# MainBoard_Sheet1.net
KiCad netlist of a schematic drawn in Altium Designer
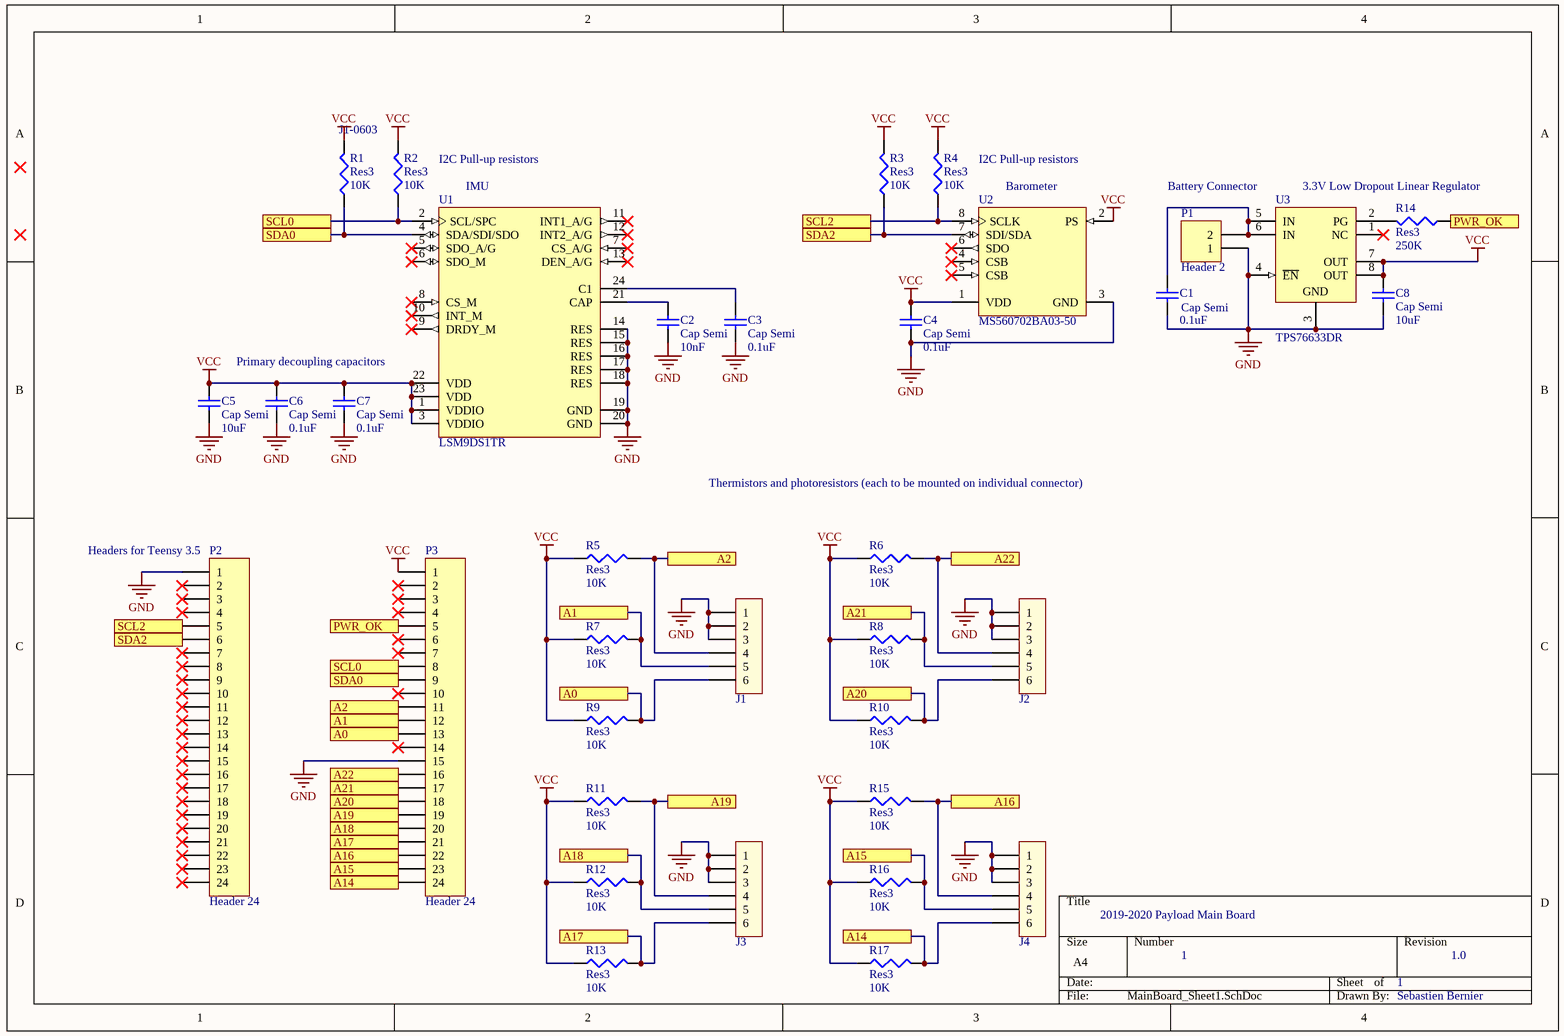
[diagram p0: MainBoard_Sheet1.SchDoc]

(export (version "E")
  (design (tool "Eeschema 10.0.6"))
  (components
    (comp (ref "C1")
      (value "Cap Semi")
      (footprint "C1206")
      (description "Capacitor (Semiconductor SIM Model)")
      (fields (field (name "ALTIUM_VALUE") "0.1uF") (field (name "PUBLISHER") "Altium Limited"))
      (libsource (lib "Miscellaneous Devices") (part "Cap Semi"))
    )
    (comp (ref "C2")
      (value "Cap Semi")
      (footprint "C1206")
      (description "Capacitor (Semiconductor SIM Model)")
      (fields (field (name "ALTIUM_VALUE") "10nF") (field (name "PUBLISHER") "Altium Limited"))
      (libsource (lib "Miscellaneous Devices") (part "Cap Semi"))
    )
    (comp (ref "C3")
      (value "Cap Semi")
      (footprint "C1206")
      (description "Capacitor (Semiconductor SIM Model)")
      (fields (field (name "ALTIUM_VALUE") "0.1uF") (field (name "PUBLISHER") "Altium Limited"))
      (libsource (lib "Miscellaneous Devices") (part "Cap Semi"))
    )
    (comp (ref "C4")
      (value "Cap Semi")
      (footprint "C1206")
      (description "Capacitor (Semiconductor SIM Model)")
      (fields (field (name "ALTIUM_VALUE") "0.1uF") (field (name "PUBLISHER") "Altium Limited"))
      (libsource (lib "Miscellaneous Devices") (part "Cap Semi"))
    )
    (comp (ref "C5")
      (value "Cap Semi")
      (footprint "C1206")
      (description "Capacitor (Semiconductor SIM Model)")
      (fields (field (name "ALTIUM_VALUE") "10uF") (field (name "PUBLISHER") "Altium Limited"))
      (libsource (lib "Miscellaneous Devices") (part "Cap Semi"))
    )
    (comp (ref "C6")
      (value "Cap Semi")
      (footprint "C1206")
      (description "Capacitor (Semiconductor SIM Model)")
      (fields (field (name "ALTIUM_VALUE") "0.1uF") (field (name "PUBLISHER") "Altium Limited"))
      (libsource (lib "Miscellaneous Devices") (part "Cap Semi"))
    )
    (comp (ref "C7")
      (value "Cap Semi")
      (footprint "C1206")
      (description "Capacitor (Semiconductor SIM Model)")
      (fields (field (name "ALTIUM_VALUE") "0.1uF") (field (name "PUBLISHER") "Altium Limited"))
      (libsource (lib "Miscellaneous Devices") (part "Cap Semi"))
    )
    (comp (ref "C8")
      (value "Cap Semi")
      (footprint "C1206")
      (description "Capacitor (Semiconductor SIM Model)")
      (fields (field (name "ALTIUM_VALUE") "10uF") (field (name "PUBLISHER") "Altium Limited"))
      (libsource (lib "Miscellaneous Devices") (part "Cap Semi"))
    )
    (comp (ref "J1")
      (value "0430450600")
      (footprint "0430450600")
      (description "CONN HEADER R/A 6POS 3MM")
      (fields (field (name "MANUFACTURER") "Molex"))
      (libsource (lib "SOARSchematics") (part "0430450600"))
    )
    (comp (ref "J2")
      (value "0430450600")
      (footprint "0430450600")
      (description "CONN HEADER R/A 6POS 3MM")
      (fields (field (name "MANUFACTURER") "Molex"))
      (libsource (lib "SOARSchematics") (part "0430450600"))
    )
    (comp (ref "J3")
      (value "0430450600")
      (footprint "0430450600")
      (description "CONN HEADER R/A 6POS 3MM")
      (fields (field (name "MANUFACTURER") "Molex"))
      (libsource (lib "SOARSchematics") (part "0430450600"))
    )
    (comp (ref "J4")
      (value "0430450600")
      (footprint "0430450600")
      (description "CONN HEADER R/A 6POS 3MM")
      (fields (field (name "MANUFACTURER") "Molex"))
      (libsource (lib "SOARSchematics") (part "0430450600"))
    )
    (comp (ref "P1")
      (value "Header 2")
      (footprint "HDR1X2")
      (description "Header, 2-Pin")
      (fields (field (name "PUBLISHER") "Altium Limited"))
      (libsource (lib "Miscellaneous Connectors") (part "Header 2"))
    )
    (comp (ref "P2")
      (value "Header 24")
      (footprint "HDR1X24")
      (description "Header, 24-Pin")
      (fields (field (name "PUBLISHER") "Altium Limited"))
      (libsource (lib "Miscellaneous Connectors") (part "Header 24"))
    )
    (comp (ref "P3")
      (value "Header 24")
      (footprint "HDR1X24")
      (description "Header, 24-Pin")
      (fields (field (name "PUBLISHER") "Altium Limited"))
      (libsource (lib "Miscellaneous Connectors") (part "Header 24"))
    )
    (comp (ref "R1")
      (value "Res3")
      (footprint "J1-0603")
      (description "Resistor")
      (fields
        (field (name "PACKAGEREFERENCE") "J1-0603")
        (field (name "ALTIUM_VALUE") "10K")
        (field (name "PUBLISHER") "Altium Limited")
      )
      (libsource (lib "Miscellaneous Devices") (part "Res3"))
    )
    (comp (ref "R2")
      (value "Res3")
      (footprint "J1-0603")
      (description "Resistor")
      (fields (field (name "ALTIUM_VALUE") "10K") (field (name "PUBLISHER") "Altium Limited"))
      (libsource (lib "Miscellaneous Devices") (part "Res3"))
    )
    (comp (ref "R3")
      (value "Res3")
      (footprint "J1-0603")
      (description "Resistor")
      (fields (field (name "ALTIUM_VALUE") "10K") (field (name "PUBLISHER") "Altium Limited"))
      (libsource (lib "Miscellaneous Devices") (part "Res3"))
    )
    (comp (ref "R4")
      (value "Res3")
      (footprint "J1-0603")
      (description "Resistor")
      (fields (field (name "ALTIUM_VALUE") "10K") (field (name "PUBLISHER") "Altium Limited"))
      (libsource (lib "Miscellaneous Devices") (part "Res3"))
    )
    (comp (ref "R5")
      (value "Res3")
      (footprint "J1-0603")
      (description "Resistor")
      (fields (field (name "ALTIUM_VALUE") "10K") (field (name "PUBLISHER") "Altium Limited"))
      (libsource (lib "Miscellaneous Devices") (part "Res3"))
    )
    (comp (ref "R6")
      (value "Res3")
      (footprint "J1-0603")
      (description "Resistor")
      (fields (field (name "ALTIUM_VALUE") "10K") (field (name "PUBLISHER") "Altium Limited"))
      (libsource (lib "Miscellaneous Devices") (part "Res3"))
    )
    (comp (ref "R7")
      (value "Res3")
      (footprint "J1-0603")
      (description "Resistor")
      (fields (field (name "ALTIUM_VALUE") "10K") (field (name "PUBLISHER") "Altium Limited"))
      (libsource (lib "Miscellaneous Devices") (part "Res3"))
    )
    (comp (ref "R8")
      (value "Res3")
      (footprint "J1-0603")
      (description "Resistor")
      (fields (field (name "ALTIUM_VALUE") "10K") (field (name "PUBLISHER") "Altium Limited"))
      (libsource (lib "Miscellaneous Devices") (part "Res3"))
    )
    (comp (ref "R9")
      (value "Res3")
      (footprint "J1-0603")
      (description "Resistor")
      (fields (field (name "ALTIUM_VALUE") "10K") (field (name "PUBLISHER") "Altium Limited"))
      (libsource (lib "Miscellaneous Devices") (part "Res3"))
    )
    (comp (ref "R10")
      (value "Res3")
      (footprint "J1-0603")
      (description "Resistor")
      (fields (field (name "ALTIUM_VALUE") "10K") (field (name "PUBLISHER") "Altium Limited"))
      (libsource (lib "Miscellaneous Devices") (part "Res3"))
    )
    (comp (ref "R11")
      (value "Res3")
      (footprint "J1-0603")
      (description "Resistor")
      (fields (field (name "ALTIUM_VALUE") "10K") (field (name "PUBLISHER") "Altium Limited"))
      (libsource (lib "Miscellaneous Devices") (part "Res3"))
    )
    (comp (ref "R12")
      (value "Res3")
      (footprint "J1-0603")
      (description "Resistor")
      (fields (field (name "ALTIUM_VALUE") "10K") (field (name "PUBLISHER") "Altium Limited"))
      (libsource (lib "Miscellaneous Devices") (part "Res3"))
    )
    (comp (ref "R13")
      (value "Res3")
      (footprint "J1-0603")
      (description "Resistor")
      (fields (field (name "ALTIUM_VALUE") "10K") (field (name "PUBLISHER") "Altium Limited"))
      (libsource (lib "Miscellaneous Devices") (part "Res3"))
    )
    (comp (ref "R14")
      (value "Res3")
      (footprint "J1-0603")
      (description "Resistor")
      (fields (field (name "ALTIUM_VALUE") "250K") (field (name "PUBLISHER") "Altium Limited"))
      (libsource (lib "Miscellaneous Devices") (part "Res3"))
    )
    (comp (ref "R15")
      (value "Res3")
      (footprint "J1-0603")
      (description "Resistor")
      (fields (field (name "ALTIUM_VALUE") "10K") (field (name "PUBLISHER") "Altium Limited"))
      (libsource (lib "Miscellaneous Devices") (part "Res3"))
    )
    (comp (ref "R16")
      (value "Res3")
      (footprint "J1-0603")
      (description "Resistor")
      (fields (field (name "ALTIUM_VALUE") "10K") (field (name "PUBLISHER") "Altium Limited"))
      (libsource (lib "Miscellaneous Devices") (part "Res3"))
    )
    (comp (ref "R17")
      (value "Res3")
      (footprint "J1-0603")
      (description "Resistor")
      (fields (field (name "ALTIUM_VALUE") "10K") (field (name "PUBLISHER") "Altium Limited"))
      (libsource (lib "Miscellaneous Devices") (part "Res3"))
    )
    (comp (ref "U1")
      (value "LSM9DS1TR")
      (footprint "STM-LGA-24_3500X3000X1000")
      (fields (field (name "PARTNUMBER") "LSM9DS1") (field (name "MANUFACTURER") "STMicroelectronics"))
      (libsource (lib "Altium Content Vault") (part "STM-LSM9DS1-24"))
    )
    (comp (ref "U2")
      (value "MS560702BA03-50")
      (footprint "TECO-MS560702BA03-50_V")
      (fields (field (name "MANUFACTURER") "TE Connectivity"))
      (libsource (lib "Altium Content Vault") (part "TECO-MS560702BA03-8"))
    )
    (comp (ref "U3")
      (value "TPS76633DR")
      (footprint "D0008A_N")
      (fields (field (name "MANUFACTURER") "Texas Instruments"))
      (libsource (lib "Altium Content Vault") (part "TI-TPS76XXX-D8"))
    )
  )
  (nets
    (net (code "1") (name "/A0") (class "Default")
      (node (ref "J1") (pin "6") (pinfunction "6_6") (pintype "passive"))
      (node (ref "P3") (pin "13") (pinfunction "13_13") (pintype "passive"))
      (node (ref "R9") (pin "2") (pinfunction "2_2") (pintype "passive"))
    )
    (net (code "2") (name "/A1") (class "Default")
      (node (ref "J1") (pin "5") (pinfunction "5_5") (pintype "passive"))
      (node (ref "P3") (pin "12") (pinfunction "12_12") (pintype "passive"))
      (node (ref "R7") (pin "2") (pinfunction "2_2") (pintype "passive"))
    )
    (net (code "3") (name "/A2") (class "Default")
      (node (ref "J1") (pin "4") (pinfunction "4_4") (pintype "passive"))
      (node (ref "P3") (pin "11") (pinfunction "11_11") (pintype "passive"))
      (node (ref "R5") (pin "2") (pinfunction "2_2") (pintype "passive"))
    )
    (net (code "4") (name "/A14") (class "Default")
      (node (ref "J4") (pin "6") (pinfunction "6_6") (pintype "passive"))
      (node (ref "P3") (pin "24") (pinfunction "24_24") (pintype "passive"))
      (node (ref "R17") (pin "2") (pinfunction "2_2") (pintype "passive"))
    )
    (net (code "5") (name "/A15") (class "Default")
      (node (ref "J4") (pin "5") (pinfunction "5_5") (pintype "passive"))
      (node (ref "P3") (pin "23") (pinfunction "23_23") (pintype "passive"))
      (node (ref "R16") (pin "2") (pinfunction "2_2") (pintype "passive"))
    )
    (net (code "6") (name "/A16") (class "Default")
      (node (ref "J4") (pin "4") (pinfunction "4_4") (pintype "passive"))
      (node (ref "P3") (pin "22") (pinfunction "22_22") (pintype "passive"))
      (node (ref "R15") (pin "2") (pinfunction "2_2") (pintype "passive"))
    )
    (net (code "7") (name "/A17") (class "Default")
      (node (ref "J3") (pin "6") (pinfunction "6_6") (pintype "passive"))
      (node (ref "P3") (pin "21") (pinfunction "21_21") (pintype "passive"))
      (node (ref "R13") (pin "2") (pinfunction "2_2") (pintype "passive"))
    )
    (net (code "8") (name "/A18") (class "Default")
      (node (ref "J3") (pin "5") (pinfunction "5_5") (pintype "passive"))
      (node (ref "P3") (pin "20") (pinfunction "20_20") (pintype "passive"))
      (node (ref "R12") (pin "2") (pinfunction "2_2") (pintype "passive"))
    )
    (net (code "9") (name "/A19") (class "Default")
      (node (ref "J3") (pin "4") (pinfunction "4_4") (pintype "passive"))
      (node (ref "P3") (pin "19") (pinfunction "19_19") (pintype "passive"))
      (node (ref "R11") (pin "2") (pinfunction "2_2") (pintype "passive"))
    )
    (net (code "10") (name "/A20") (class "Default")
      (node (ref "J2") (pin "6") (pinfunction "6_6") (pintype "passive"))
      (node (ref "P3") (pin "18") (pinfunction "18_18") (pintype "passive"))
      (node (ref "R10") (pin "2") (pinfunction "2_2") (pintype "passive"))
    )
    (net (code "11") (name "/A21") (class "Default")
      (node (ref "J2") (pin "5") (pinfunction "5_5") (pintype "passive"))
      (node (ref "P3") (pin "17") (pinfunction "17_17") (pintype "passive"))
      (node (ref "R8") (pin "2") (pinfunction "2_2") (pintype "passive"))
    )
    (net (code "12") (name "/A22") (class "Default")
      (node (ref "J2") (pin "4") (pinfunction "4_4") (pintype "passive"))
      (node (ref "P3") (pin "16") (pinfunction "16_16") (pintype "passive"))
      (node (ref "R6") (pin "2") (pinfunction "2_2") (pintype "passive"))
    )
    (net (code "13") (name "/PWR_OK") (class "Default")
      (node (ref "P3") (pin "5") (pinfunction "5_5") (pintype "passive"))
      (node (ref "R14") (pin "1") (pinfunction "1_1") (pintype "passive"))
    )
    (net (code "14") (name "/SCL0") (class "Default")
      (node (ref "P3") (pin "8") (pinfunction "8_8") (pintype "passive"))
      (node (ref "R2") (pin "1") (pinfunction "1_1") (pintype "passive"))
      (node (ref "U1") (pin "2") (pinfunction "SCL/SPC_2") (pintype "input"))
    )
    (net (code "15") (name "/SCL2") (class "Default")
      (node (ref "P2") (pin "5") (pinfunction "5_5") (pintype "passive"))
      (node (ref "R4") (pin "1") (pinfunction "1_1") (pintype "passive"))
      (node (ref "U2") (pin "8") (pinfunction "SCLK_8") (pintype "input"))
    )
    (net (code "16") (name "/SDA0") (class "Default")
      (node (ref "P3") (pin "9") (pinfunction "9_9") (pintype "passive"))
      (node (ref "R1") (pin "1") (pinfunction "1_1") (pintype "passive"))
      (node (ref "U1") (pin "4") (pinfunction "SDA/SDI/SDO_4") (pintype "bidirectional"))
    )
    (net (code "17") (name "/SDA2") (class "Default")
      (node (ref "P2") (pin "6") (pinfunction "6_6") (pintype "passive"))
      (node (ref "R3") (pin "1") (pinfunction "1_1") (pintype "passive"))
      (node (ref "U2") (pin "7") (pinfunction "SDI/SDA_7") (pintype "bidirectional"))
    )
    (net (code "18") (name "GND") (class "Default")
      (node (ref "C1") (pin "1") (pinfunction "1_1") (pintype "passive"))
      (node (ref "C2") (pin "1") (pinfunction "1_1") (pintype "passive"))
      (node (ref "C3") (pin "1") (pinfunction "1_1") (pintype "passive"))
      (node (ref "C4") (pin "1") (pinfunction "1_1") (pintype "passive"))
      (node (ref "C5") (pin "1") (pinfunction "1_1") (pintype "passive"))
      (node (ref "C6") (pin "1") (pinfunction "1_1") (pintype "passive"))
      (node (ref "C7") (pin "1") (pinfunction "1_1") (pintype "passive"))
      (node (ref "C8") (pin "1") (pinfunction "1_1") (pintype "passive"))
      (node (ref "J1") (pin "1") (pinfunction "1_1") (pintype "passive"))
      (node (ref "J1") (pin "2") (pinfunction "2_2") (pintype "passive"))
      (node (ref "J1") (pin "3") (pinfunction "3_3") (pintype "passive"))
      (node (ref "J2") (pin "1") (pinfunction "1_1") (pintype "passive"))
      (node (ref "J2") (pin "2") (pinfunction "2_2") (pintype "passive"))
      (node (ref "J2") (pin "3") (pinfunction "3_3") (pintype "passive"))
      (node (ref "J3") (pin "1") (pinfunction "1_1") (pintype "passive"))
      (node (ref "J3") (pin "2") (pinfunction "2_2") (pintype "passive"))
      (node (ref "J3") (pin "3") (pinfunction "3_3") (pintype "passive"))
      (node (ref "J4") (pin "1") (pinfunction "1_1") (pintype "passive"))
      (node (ref "J4") (pin "2") (pinfunction "2_2") (pintype "passive"))
      (node (ref "J4") (pin "3") (pinfunction "3_3") (pintype "passive"))
      (node (ref "P1") (pin "1") (pinfunction "1_1") (pintype "passive"))
      (node (ref "P2") (pin "1") (pinfunction "1_1") (pintype "passive"))
      (node (ref "P3") (pin "15") (pinfunction "15_15") (pintype "passive"))
      (node (ref "U1") (pin "14") (pinfunction "RES_14") (pintype "passive"))
      (node (ref "U1") (pin "15") (pinfunction "RES_15") (pintype "passive"))
      (node (ref "U1") (pin "16") (pinfunction "RES_16") (pintype "passive"))
      (node (ref "U1") (pin "17") (pinfunction "RES_17") (pintype "passive"))
      (node (ref "U1") (pin "18") (pinfunction "RES_18") (pintype "passive"))
      (node (ref "U1") (pin "19") (pinfunction "GND_19") (pintype "power_in"))
      (node (ref "U1") (pin "20") (pinfunction "GND_20") (pintype "power_in"))
      (node (ref "U2") (pin "3") (pinfunction "GND_3") (pintype "power_in"))
      (node (ref "U3") (pin "3") (pinfunction "GND_3") (pintype "power_in"))
      (node (ref "U3") (pin "4") (pinfunction "~{EN}_4") (pintype "input"))
    )
    (net (code "19") (name "Net-(C1-Pad2)") (class "Default")
      (node (ref "C1") (pin "2") (pinfunction "2_2") (pintype "passive"))
      (node (ref "P1") (pin "2") (pinfunction "2_2") (pintype "passive"))
      (node (ref "U3") (pin "5") (pinfunction "IN_5") (pintype "power_in"))
      (node (ref "U3") (pin "6") (pinfunction "IN_6") (pintype "power_in"))
    )
    (net (code "20") (name "Net-(U1-C1)") (class "Default")
      (node (ref "C3") (pin "2") (pinfunction "2_2") (pintype "passive"))
      (node (ref "U1") (pin "24") (pinfunction "C1_24") (pintype "passive"))
    )
    (net (code "21") (name "Net-(U1-CAP)") (class "Default")
      (node (ref "C2") (pin "2") (pinfunction "2_2") (pintype "passive"))
      (node (ref "U1") (pin "21") (pinfunction "CAP_21") (pintype "passive"))
    )
    (net (code "22") (name "Net-(U3-PG)") (class "Default")
      (node (ref "R14") (pin "2") (pinfunction "2_2") (pintype "passive"))
      (node (ref "U3") (pin "2") (pinfunction "PG_2") (pintype "tri_state"))
    )
    (net (code "23") (name "VCC") (class "Default")
      (node (ref "C4") (pin "2") (pinfunction "2_2") (pintype "passive"))
      (node (ref "C5") (pin "2") (pinfunction "2_2") (pintype "passive"))
      (node (ref "C6") (pin "2") (pinfunction "2_2") (pintype "passive"))
      (node (ref "C7") (pin "2") (pinfunction "2_2") (pintype "passive"))
      (node (ref "C8") (pin "2") (pinfunction "2_2") (pintype "passive"))
      (node (ref "P3") (pin "1") (pinfunction "1_1") (pintype "passive"))
      (node (ref "R1") (pin "2") (pinfunction "2_2") (pintype "passive"))
      (node (ref "R10") (pin "1") (pinfunction "1_1") (pintype "passive"))
      (node (ref "R11") (pin "1") (pinfunction "1_1") (pintype "passive"))
      (node (ref "R12") (pin "1") (pinfunction "1_1") (pintype "passive"))
      (node (ref "R13") (pin "1") (pinfunction "1_1") (pintype "passive"))
      (node (ref "R15") (pin "1") (pinfunction "1_1") (pintype "passive"))
      (node (ref "R16") (pin "1") (pinfunction "1_1") (pintype "passive"))
      (node (ref "R17") (pin "1") (pinfunction "1_1") (pintype "passive"))
      (node (ref "R2") (pin "2") (pinfunction "2_2") (pintype "passive"))
      (node (ref "R3") (pin "2") (pinfunction "2_2") (pintype "passive"))
      (node (ref "R4") (pin "2") (pinfunction "2_2") (pintype "passive"))
      (node (ref "R5") (pin "1") (pinfunction "1_1") (pintype "passive"))
      (node (ref "R6") (pin "1") (pinfunction "1_1") (pintype "passive"))
      (node (ref "R7") (pin "1") (pinfunction "1_1") (pintype "passive"))
      (node (ref "R8") (pin "1") (pinfunction "1_1") (pintype "passive"))
      (node (ref "R9") (pin "1") (pinfunction "1_1") (pintype "passive"))
      (node (ref "U1") (pin "1") (pinfunction "VDDIO_1") (pintype "power_in"))
      (node (ref "U1") (pin "22") (pinfunction "VDD_22") (pintype "power_in"))
      (node (ref "U1") (pin "23") (pinfunction "VDD_23") (pintype "power_in"))
      (node (ref "U1") (pin "3") (pinfunction "VDDIO_3") (pintype "power_in"))
      (node (ref "U2") (pin "1") (pinfunction "VDD_1") (pintype "power_in"))
      (node (ref "U2") (pin "2") (pinfunction "PS_2") (pintype "input"))
      (node (ref "U3") (pin "7") (pinfunction "OUT_7") (pintype "power_in"))
      (node (ref "U3") (pin "8") (pinfunction "OUT_8") (pintype "power_in"))
    )
    (net (code "24") (name "unconnected-(P2-Pad2)") (class "Default")
      (node (ref "P2") (pin "2") (pinfunction "2_2") (pintype "passive+no_connect"))
    )
    (net (code "25") (name "unconnected-(P2-Pad3)") (class "Default")
      (node (ref "P2") (pin "3") (pinfunction "3_3") (pintype "passive+no_connect"))
    )
    (net (code "26") (name "unconnected-(P2-Pad4)") (class "Default")
      (node (ref "P2") (pin "4") (pinfunction "4_4") (pintype "passive+no_connect"))
    )
    (net (code "27") (name "unconnected-(P2-Pad7)") (class "Default")
      (node (ref "P2") (pin "7") (pinfunction "7_7") (pintype "passive+no_connect"))
    )
    (net (code "28") (name "unconnected-(P2-Pad8)") (class "Default")
      (node (ref "P2") (pin "8") (pinfunction "8_8") (pintype "passive+no_connect"))
    )
    (net (code "29") (name "unconnected-(P2-Pad9)") (class "Default")
      (node (ref "P2") (pin "9") (pinfunction "9_9") (pintype "passive+no_connect"))
    )
    (net (code "30") (name "unconnected-(P2-Pad10)") (class "Default")
      (node (ref "P2") (pin "10") (pinfunction "10_10") (pintype "passive+no_connect"))
    )
    (net (code "31") (name "unconnected-(P2-Pad11)") (class "Default")
      (node (ref "P2") (pin "11") (pinfunction "11_11") (pintype "passive+no_connect"))
    )
    (net (code "32") (name "unconnected-(P2-Pad12)") (class "Default")
      (node (ref "P2") (pin "12") (pinfunction "12_12") (pintype "passive+no_connect"))
    )
    (net (code "33") (name "unconnected-(P2-Pad13)") (class "Default")
      (node (ref "P2") (pin "13") (pinfunction "13_13") (pintype "passive+no_connect"))
    )
    (net (code "34") (name "unconnected-(P2-Pad14)") (class "Default")
      (node (ref "P2") (pin "14") (pinfunction "14_14") (pintype "passive+no_connect"))
    )
    (net (code "35") (name "unconnected-(P2-Pad15)") (class "Default")
      (node (ref "P2") (pin "15") (pinfunction "15_15") (pintype "passive+no_connect"))
    )
    (net (code "36") (name "unconnected-(P2-Pad16)") (class "Default")
      (node (ref "P2") (pin "16") (pinfunction "16_16") (pintype "passive+no_connect"))
    )
    (net (code "37") (name "unconnected-(P2-Pad17)") (class "Default")
      (node (ref "P2") (pin "17") (pinfunction "17_17") (pintype "passive+no_connect"))
    )
    (net (code "38") (name "unconnected-(P2-Pad18)") (class "Default")
      (node (ref "P2") (pin "18") (pinfunction "18_18") (pintype "passive+no_connect"))
    )
    (net (code "39") (name "unconnected-(P2-Pad19)") (class "Default")
      (node (ref "P2") (pin "19") (pinfunction "19_19") (pintype "passive+no_connect"))
    )
    (net (code "40") (name "unconnected-(P2-Pad20)") (class "Default")
      (node (ref "P2") (pin "20") (pinfunction "20_20") (pintype "passive+no_connect"))
    )
    (net (code "41") (name "unconnected-(P2-Pad21)") (class "Default")
      (node (ref "P2") (pin "21") (pinfunction "21_21") (pintype "passive+no_connect"))
    )
    (net (code "42") (name "unconnected-(P2-Pad22)") (class "Default")
      (node (ref "P2") (pin "22") (pinfunction "22_22") (pintype "passive+no_connect"))
    )
    (net (code "43") (name "unconnected-(P2-Pad23)") (class "Default")
      (node (ref "P2") (pin "23") (pinfunction "23_23") (pintype "passive+no_connect"))
    )
    (net (code "44") (name "unconnected-(P2-Pad24)") (class "Default")
      (node (ref "P2") (pin "24") (pinfunction "24_24") (pintype "passive+no_connect"))
    )
    (net (code "45") (name "unconnected-(P3-Pad2)") (class "Default")
      (node (ref "P3") (pin "2") (pinfunction "2_2") (pintype "passive+no_connect"))
    )
    (net (code "46") (name "unconnected-(P3-Pad3)") (class "Default")
      (node (ref "P3") (pin "3") (pinfunction "3_3") (pintype "passive+no_connect"))
    )
    (net (code "47") (name "unconnected-(P3-Pad4)") (class "Default")
      (node (ref "P3") (pin "4") (pinfunction "4_4") (pintype "passive+no_connect"))
    )
    (net (code "48") (name "unconnected-(P3-Pad6)") (class "Default")
      (node (ref "P3") (pin "6") (pinfunction "6_6") (pintype "passive+no_connect"))
    )
    (net (code "49") (name "unconnected-(P3-Pad7)") (class "Default")
      (node (ref "P3") (pin "7") (pinfunction "7_7") (pintype "passive+no_connect"))
    )
    (net (code "50") (name "unconnected-(P3-Pad10)") (class "Default")
      (node (ref "P3") (pin "10") (pinfunction "10_10") (pintype "passive+no_connect"))
    )
    (net (code "51") (name "unconnected-(P3-Pad14)") (class "Default")
      (node (ref "P3") (pin "14") (pinfunction "14_14") (pintype "passive+no_connect"))
    )
    (net (code "52") (name "unconnected-(U1-CS_A{slash}G-Pad7)") (class "Default")
      (node (ref "U1") (pin "7") (pinfunction "CS_A/G_7") (pintype "input+no_connect"))
    )
    (net (code "53") (name "unconnected-(U1-CS_M-Pad8)") (class "Default")
      (node (ref "U1") (pin "8") (pinfunction "CS_M_8") (pintype "input+no_connect"))
    )
    (net (code "54") (name "unconnected-(U1-DEN_A{slash}G-Pad13)") (class "Default")
      (node (ref "U1") (pin "13") (pinfunction "DEN_A/G_13") (pintype "input+no_connect"))
    )
    (net (code "55") (name "unconnected-(U1-DRDY_M-Pad9)") (class "Default")
      (node (ref "U1") (pin "9") (pinfunction "DRDY_M_9") (pintype "output+no_connect"))
    )
    (net (code "56") (name "unconnected-(U1-INT1_A{slash}G-Pad11)") (class "Default")
      (node (ref "U1") (pin "11") (pinfunction "INT1_A/G_11") (pintype "output+no_connect"))
    )
    (net (code "57") (name "unconnected-(U1-INT2_A{slash}G-Pad12)") (class "Default")
      (node (ref "U1") (pin "12") (pinfunction "INT2_A/G_12") (pintype "output+no_connect"))
    )
    (net (code "58") (name "unconnected-(U1-INT_M-Pad10)") (class "Default")
      (node (ref "U1") (pin "10") (pinfunction "INT_M_10") (pintype "output+no_connect"))
    )
    (net (code "59") (name "unconnected-(U1-SDO_A{slash}G-Pad5)") (class "Default")
      (node (ref "U1") (pin "5") (pinfunction "SDO_A/G_5") (pintype "bidirectional+no_connect"))
    )
    (net (code "60") (name "unconnected-(U1-SDO_M-Pad6)") (class "Default")
      (node (ref "U1") (pin "6") (pinfunction "SDO_M_6") (pintype "bidirectional+no_connect"))
    )
    (net (code "61") (name "unconnected-(U2-CSB-Pad4)") (class "Default")
      (node (ref "U2") (pin "4") (pinfunction "CSB_4") (pintype "input+no_connect"))
    )
    (net (code "62") (name "unconnected-(U2-CSB-Pad5)") (class "Default")
      (node (ref "U2") (pin "5") (pinfunction "CSB_5") (pintype "input+no_connect"))
    )
    (net (code "63") (name "unconnected-(U2-SDO-Pad6)") (class "Default")
      (node (ref "U2") (pin "6") (pinfunction "SDO_6") (pintype "output+no_connect"))
    )
    (net (code "64") (name "unconnected-(U3-NC-Pad1)") (class "Default")
      (node (ref "U3") (pin "1") (pinfunction "NC_1") (pintype "passive+no_connect"))
    )
  )
)
